# heehaw09.net
KiCad netlist of a schematic drawn in EAGLE
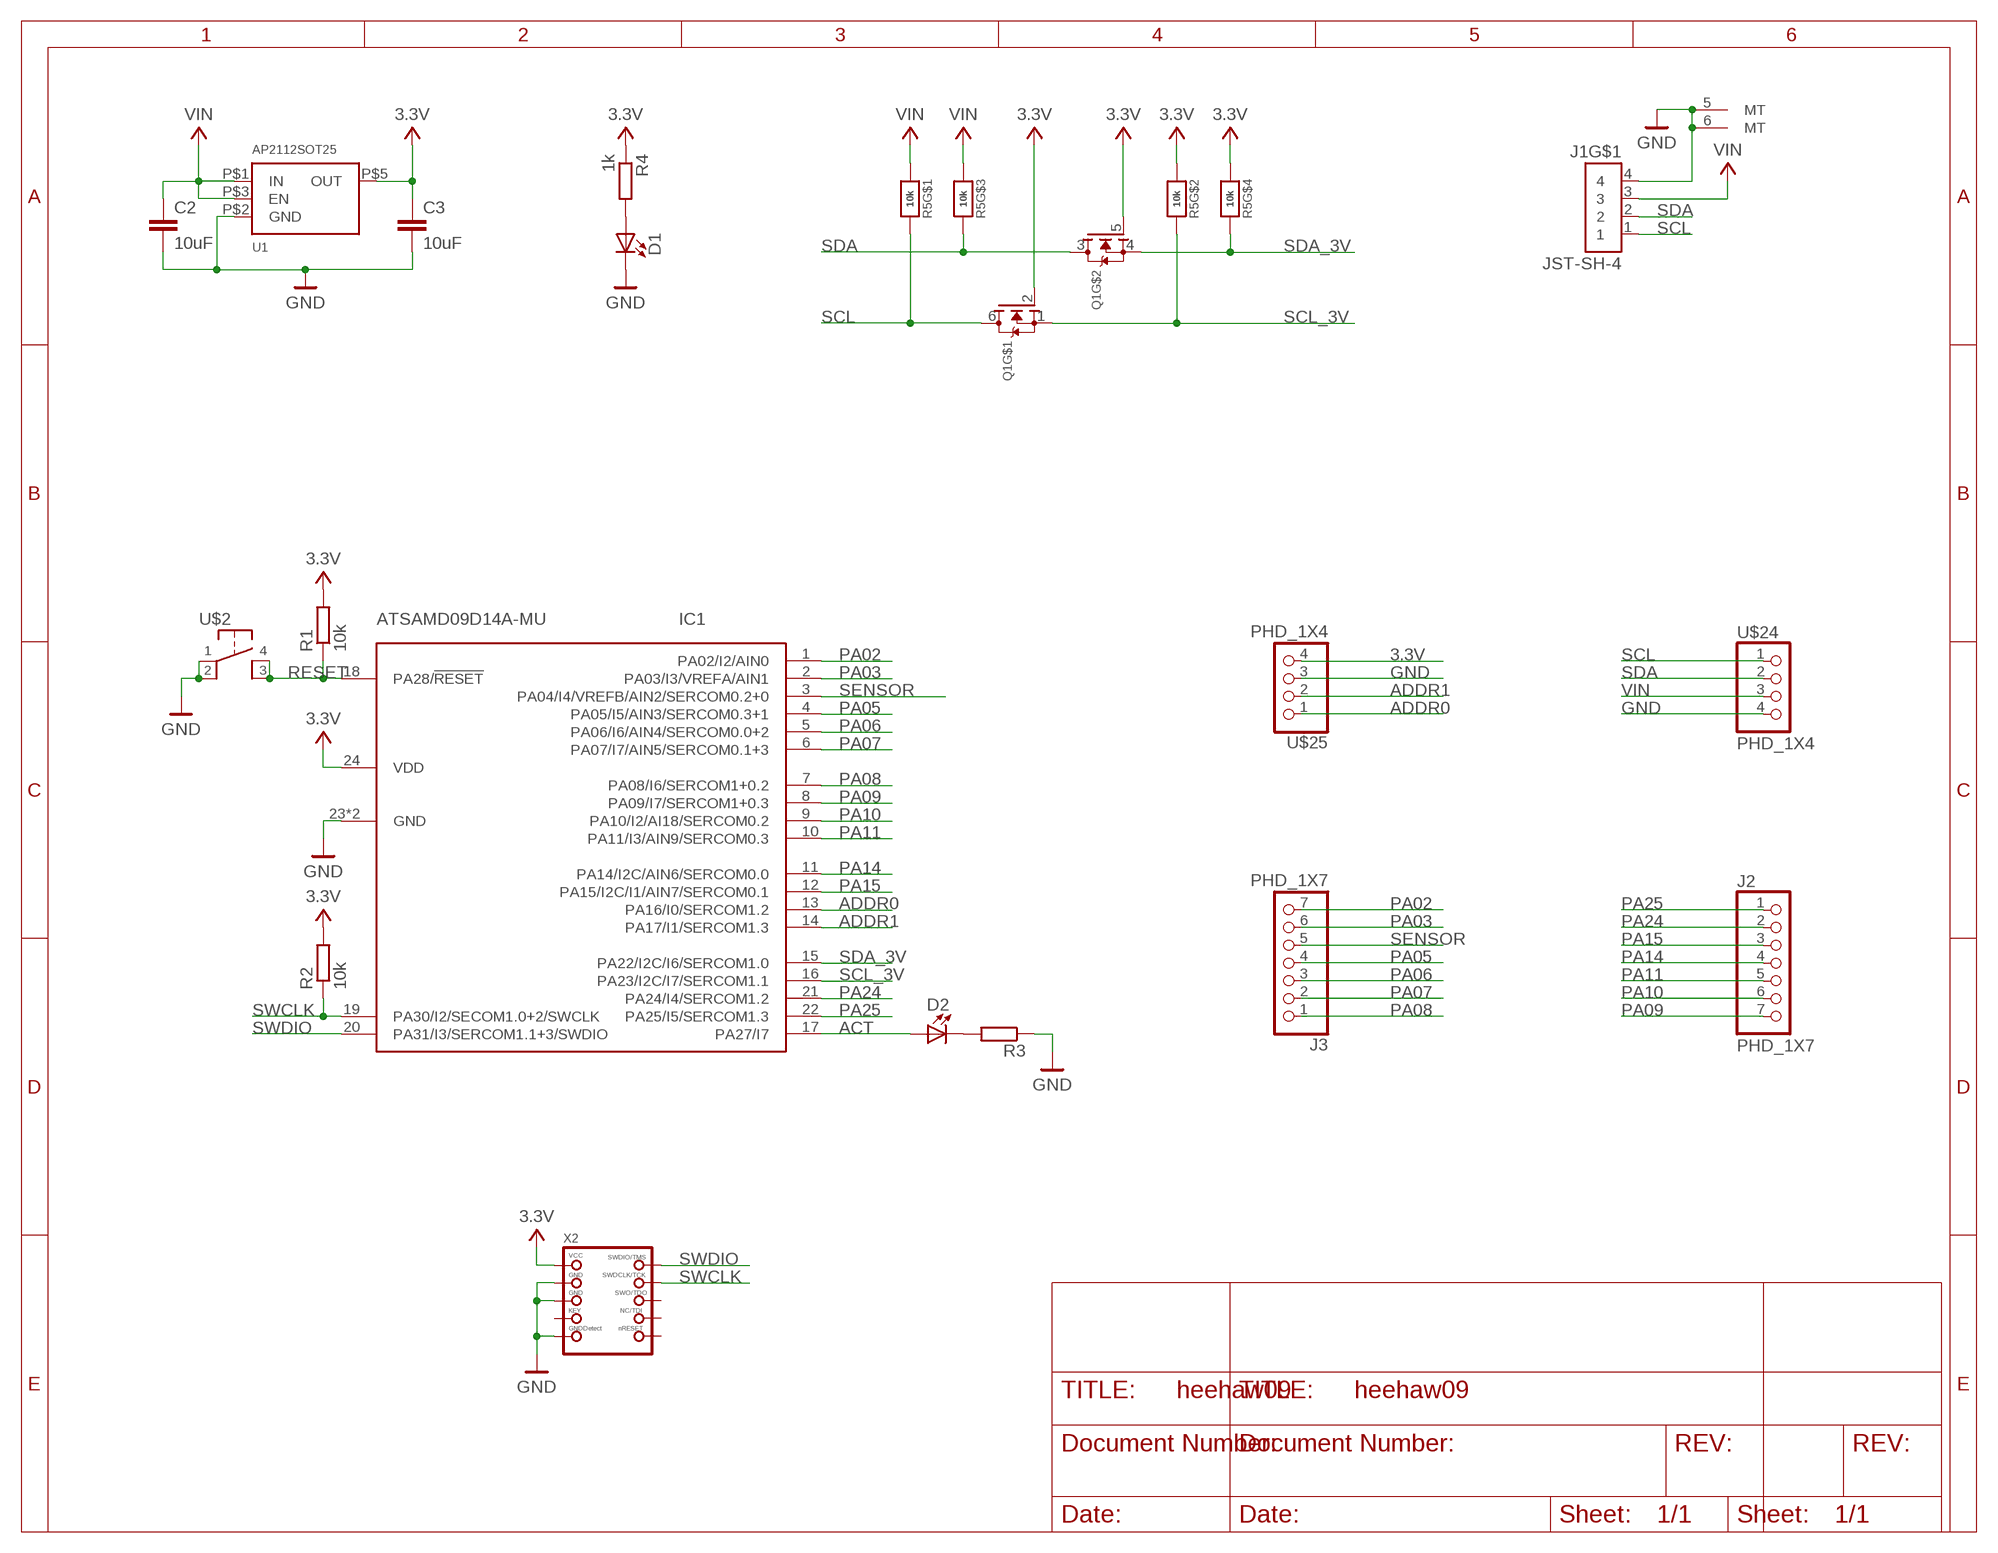
[diagram p0: schematic, sheet 1]

(export (version "E")
  (design (tool "Eeschema 10.0.6"))
  (components
    (comp (ref "C2")
      (value "10uF")
      (footprint "eagle-import:C0603")
      (libsource (lib "eagle-import") (part "C-EUC0603"))
    )
    (comp (ref "C3")
      (value "10uF")
      (footprint "eagle-import:C0603")
      (libsource (lib "eagle-import") (part "C-EUC0603"))
    )
    (comp (ref "D1")
      (value "SMD_LED0603")
      (footprint "eagle-import:LED0603")
      (libsource (lib "eagle-import") (part "SMD_LED0603"))
    )
    (comp (ref "D2")
      (value "SMD_LED0603")
      (footprint "eagle-import:LED0603")
      (libsource (lib "eagle-import") (part "SMD_LED0603"))
    )
    (comp (ref "IC1")
      (value "ATSAMD09D14A-MU")
      (footprint "eagle-import:QFN24_4MM")
      (libsource (lib "eagle-import") (part "ATSAMD09D14A-MU"))
    )
    (comp (ref "J1")
      (value "JST-SH-4")
      (footprint "eagle-import:JST-S4B-SH-SM4-TB")
      (libsource (lib "eagle-import") (part "JST-SH-4"))
    )
    (comp (ref "J2")
      (value "PHD_1X7")
      (footprint "eagle-import:PHD_1X7")
      (libsource (lib "eagle-import") (part "PHD_1X7"))
    )
    (comp (ref "J3")
      (value "PHD_1X7")
      (footprint "eagle-import:PHD_1X7")
      (libsource (lib "eagle-import") (part "PHD_1X7"))
    )
    (comp (ref "Q1")
      (value "MOSFET-N_DUAL")
      (footprint "eagle-import:SOT363")
      (libsource (lib "eagle-import") (part "MOSFET-N_DUAL"))
    )
    (comp (ref "R1")
      (value "10k")
      (footprint "eagle-import:R0603")
      (libsource (lib "eagle-import") (part "R-EU_R0603"))
    )
    (comp (ref "R2")
      (value "10k")
      (footprint "eagle-import:R0603")
      (libsource (lib "eagle-import") (part "R-EU_R0603"))
    )
    (comp (ref "R3")
      (value "R-EU_R0603")
      (footprint "eagle-import:R0603")
      (libsource (lib "eagle-import") (part "R-EU_R0603"))
    )
    (comp (ref "R4")
      (value "1k")
      (footprint "eagle-import:R0603")
      (libsource (lib "eagle-import") (part "R-EU_R0603"))
    )
    (comp (ref "R5")
      (value "10k")
      (footprint "eagle-import:RESPACK_4X0603")
      (libsource (lib "eagle-import") (part "RESISTOR_4PACK"))
    )
    (comp (ref "U$2")
      (value "PTS647")
      (footprint "eagle-import:PTS647")
      (libsource (lib "eagle-import") (part "PTS647"))
    )
    (comp (ref "U$24")
      (value "PHD_1X4")
      (footprint "eagle-import:PHD_1X4")
      (libsource (lib "eagle-import") (part "PHD_1X4"))
    )
    (comp (ref "U$25")
      (value "PHD_1X4")
      (footprint "eagle-import:PHD_1X4")
      (libsource (lib "eagle-import") (part "PHD_1X4"))
    )
    (comp (ref "U1")
      (value "AP2112SOT25")
      (footprint "eagle-import:SOT25")
      (libsource (lib "eagle-import") (part "AP2112SOT25"))
    )
    (comp (ref "X2")
      (value "SWD_2X5")
      (footprint "eagle-import:SWD_MINI")
      (libsource (lib "eagle-import") (part "SWD_2X5"))
    )
  )
  (nets
    (net (code "1") (name "/ACT") (class "Default")
      (node (ref "D2") (pin "2") (pinfunction "A_2") (pintype "passive"))
      (node (ref "IC1") (pin "17") (pinfunction "PA27/I7_17") (pintype "bidirectional"))
    )
    (net (code "2") (name "/ADDR0") (class "Default")
      (node (ref "IC1") (pin "13") (pinfunction "PA16/I0/SERCOM1.2_13") (pintype "bidirectional"))
      (node (ref "U$25") (pin "1") (pinfunction "1_1") (pintype "passive"))
    )
    (net (code "3") (name "/ADDR1") (class "Default")
      (node (ref "IC1") (pin "14") (pinfunction "PA17/I1/SERCOM1.3_14") (pintype "bidirectional"))
      (node (ref "U$25") (pin "2") (pinfunction "2_2") (pintype "passive"))
    )
    (net (code "4") (name "/PA02") (class "Default")
      (node (ref "IC1") (pin "1") (pinfunction "PA02/I2/AIN0_1") (pintype "bidirectional"))
      (node (ref "J3") (pin "7") (pinfunction "7_7") (pintype "passive"))
    )
    (net (code "5") (name "/PA03") (class "Default")
      (node (ref "IC1") (pin "2") (pinfunction "PA03/I3/VREFA/AIN1_2") (pintype "bidirectional"))
      (node (ref "J3") (pin "6") (pinfunction "6_6") (pintype "passive"))
    )
    (net (code "6") (name "/PA05") (class "Default")
      (node (ref "IC1") (pin "4") (pinfunction "PA05/I5/AIN3/SERCOM0.3+1_4") (pintype "bidirectional"))
      (node (ref "J3") (pin "4") (pinfunction "4_4") (pintype "passive"))
    )
    (net (code "7") (name "/PA06") (class "Default")
      (node (ref "IC1") (pin "5") (pinfunction "PA06/I6/AIN4/SERCOM0.0+2_5") (pintype "bidirectional"))
      (node (ref "J3") (pin "3") (pinfunction "3_3") (pintype "passive"))
    )
    (net (code "8") (name "/PA07") (class "Default")
      (node (ref "IC1") (pin "6") (pinfunction "PA07/I7/AIN5/SERCOM0.1+3_6") (pintype "bidirectional"))
      (node (ref "J3") (pin "2") (pinfunction "2_2") (pintype "passive"))
    )
    (net (code "9") (name "/PA08") (class "Default")
      (node (ref "IC1") (pin "7") (pinfunction "PA08/I6/SERCOM1+0.2_7") (pintype "bidirectional"))
      (node (ref "J3") (pin "1") (pinfunction "1_1") (pintype "passive"))
    )
    (net (code "10") (name "/PA09") (class "Default")
      (node (ref "IC1") (pin "8") (pinfunction "PA09/I7/SERCOM1+0.3_8") (pintype "bidirectional"))
      (node (ref "J2") (pin "7") (pinfunction "7_7") (pintype "passive"))
    )
    (net (code "11") (name "/PA10") (class "Default")
      (node (ref "IC1") (pin "9") (pinfunction "PA10/I2/AI18/SERCOM0.2_9") (pintype "bidirectional"))
      (node (ref "J2") (pin "6") (pinfunction "6_6") (pintype "passive"))
    )
    (net (code "12") (name "/PA11") (class "Default")
      (node (ref "IC1") (pin "10") (pinfunction "PA11/I3/AIN9/SERCOM0.3_10") (pintype "bidirectional"))
      (node (ref "J2") (pin "5") (pinfunction "5_5") (pintype "passive"))
    )
    (net (code "13") (name "/PA14") (class "Default")
      (node (ref "IC1") (pin "11") (pinfunction "PA14/I2C/AIN6/SERCOM0.0_11") (pintype "bidirectional"))
      (node (ref "J2") (pin "4") (pinfunction "4_4") (pintype "passive"))
    )
    (net (code "14") (name "/PA15") (class "Default")
      (node (ref "IC1") (pin "12") (pinfunction "PA15/I2C/I1/AIN7/SERCOM0.1_12") (pintype "bidirectional"))
      (node (ref "J2") (pin "3") (pinfunction "3_3") (pintype "passive"))
    )
    (net (code "15") (name "/PA24") (class "Default")
      (node (ref "IC1") (pin "21") (pinfunction "PA24/I4/SERCOM1.2_21") (pintype "bidirectional"))
      (node (ref "J2") (pin "2") (pinfunction "2_2") (pintype "passive"))
    )
    (net (code "16") (name "/PA25") (class "Default")
      (node (ref "IC1") (pin "22") (pinfunction "PA25/I5/SERCOM1.3_22") (pintype "bidirectional"))
      (node (ref "J2") (pin "1") (pinfunction "1_1") (pintype "passive"))
    )
    (net (code "17") (name "/RESET") (class "Default")
      (node (ref "IC1") (pin "18") (pinfunction "PA28/~{RESET}_18") (pintype "bidirectional"))
      (node (ref "R1") (pin "1") (pinfunction "1_1") (pintype "passive"))
      (node (ref "U$2") (pin "3") (pinfunction "3_3") (pintype "bidirectional"))
      (node (ref "U$2") (pin "4") (pinfunction "4_4") (pintype "bidirectional"))
    )
    (net (code "18") (name "/SCL") (class "Default")
      (node (ref "J1") (pin "1") (pinfunction "1_1") (pintype "bidirectional"))
      (node (ref "Q1") (pin "6") (pinfunction "D_6") (pintype "bidirectional"))
      (node (ref "R5") (pin "8") (pinfunction "2_8") (pintype "passive"))
      (node (ref "U$24") (pin "1") (pinfunction "1_1") (pintype "passive"))
    )
    (net (code "19") (name "/SCL_3V") (class "Default")
      (node (ref "IC1") (pin "16") (pinfunction "PA23/I2C/I7/SERCOM1.1_16") (pintype "bidirectional"))
      (node (ref "Q1") (pin "1") (pinfunction "S_1") (pintype "bidirectional"))
      (node (ref "R5") (pin "7") (pinfunction "2_7") (pintype "passive"))
    )
    (net (code "20") (name "/SDA") (class "Default")
      (node (ref "J1") (pin "2") (pinfunction "2_2") (pintype "bidirectional"))
      (node (ref "Q1") (pin "3") (pinfunction "D_3") (pintype "bidirectional"))
      (node (ref "R5") (pin "6") (pinfunction "2_6") (pintype "passive"))
      (node (ref "U$24") (pin "2") (pinfunction "2_2") (pintype "passive"))
    )
    (net (code "21") (name "/SDA_3V") (class "Default")
      (node (ref "IC1") (pin "15") (pinfunction "PA22/I2C/I6/SERCOM1.0_15") (pintype "bidirectional"))
      (node (ref "Q1") (pin "4") (pinfunction "S_4") (pintype "bidirectional"))
      (node (ref "R5") (pin "5") (pinfunction "2_5") (pintype "passive"))
    )
    (net (code "22") (name "/SENSOR") (class "Default")
      (node (ref "IC1") (pin "3") (pinfunction "PA04/I4/VREFB/AIN2/SERCOM0.2+0_3") (pintype "bidirectional"))
      (node (ref "J3") (pin "5") (pinfunction "5_5") (pintype "passive"))
    )
    (net (code "23") (name "/SWCLK") (class "Default")
      (node (ref "IC1") (pin "19") (pinfunction "PA30/I2/SECOM1.0+2/SWCLK_19") (pintype "bidirectional"))
      (node (ref "R2") (pin "1") (pinfunction "1_1") (pintype "passive"))
      (node (ref "X2") (pin "4") (pinfunction "SWDCLK_4") (pintype "bidirectional"))
    )
    (net (code "24") (name "/SWDIO") (class "Default")
      (node (ref "IC1") (pin "20") (pinfunction "PA31/I3/SERCOM1.1+3/SWDIO_20") (pintype "bidirectional"))
      (node (ref "X2") (pin "2") (pinfunction "SWDIO_2") (pintype "bidirectional"))
    )
    (net (code "25") (name "3.3V") (class "Default")
      (node (ref "C3") (pin "1") (pinfunction "1_1") (pintype "passive"))
      (node (ref "IC1") (pin "24") (pinfunction "VDD_24") (pintype "power_in"))
      (node (ref "Q1") (pin "2") (pinfunction "G_2") (pintype "bidirectional"))
      (node (ref "Q1") (pin "5") (pinfunction "G_5") (pintype "bidirectional"))
      (node (ref "R1") (pin "2") (pinfunction "2_2") (pintype "passive"))
      (node (ref "R2") (pin "2") (pinfunction "2_2") (pintype "passive"))
      (node (ref "R4") (pin "1") (pinfunction "1_1") (pintype "passive"))
      (node (ref "R5") (pin "2") (pinfunction "1_2") (pintype "passive"))
      (node (ref "R5") (pin "4") (pinfunction "1_4") (pintype "passive"))
      (node (ref "U$25") (pin "4") (pinfunction "4_4") (pintype "passive"))
      (node (ref "U1") (pin "P$5") (pinfunction "OUT_P$5") (pintype "power_in"))
      (node (ref "X2") (pin "1") (pinfunction "VCC_1") (pintype "power_in"))
    )
    (net (code "26") (name "GND") (class "Default")
      (node (ref "C2") (pin "2") (pinfunction "2_2") (pintype "passive"))
      (node (ref "C3") (pin "2") (pinfunction "2_2") (pintype "passive"))
      (node (ref "D1") (pin "1") (pinfunction "C_1") (pintype "passive"))
      (node (ref "IC1") (pin "23") (pinfunction "GND_23") (pintype "power_in"))
      (node (ref "IC1") (pin "THERM") (pinfunction "GND_THERM") (pintype "power_in"))
      (node (ref "J1") (pin "4") (pinfunction "4_4") (pintype "bidirectional"))
      (node (ref "J1") (pin "5") (pinfunction "MT_5") (pintype "bidirectional"))
      (node (ref "J1") (pin "6") (pinfunction "MT_6") (pintype "bidirectional"))
      (node (ref "R3") (pin "1") (pinfunction "1_1") (pintype "passive"))
      (node (ref "U$2") (pin "1") (pinfunction "1_1") (pintype "bidirectional"))
      (node (ref "U$2") (pin "2") (pinfunction "2_2") (pintype "bidirectional"))
      (node (ref "U$24") (pin "4") (pinfunction "4_4") (pintype "passive"))
      (node (ref "U$25") (pin "3") (pinfunction "3_3") (pintype "passive"))
      (node (ref "U1") (pin "P$2") (pinfunction "GND_P$2") (pintype "power_in"))
      (node (ref "X2") (pin "3") (pinfunction "GND_3") (pintype "power_in"))
      (node (ref "X2") (pin "5") (pinfunction "GND_5") (pintype "power_in"))
      (node (ref "X2") (pin "9") (pinfunction "GNDDETECT_9") (pintype "bidirectional"))
    )
    (net (code "27") (name "Net-(D1-A)") (class "Default")
      (node (ref "D1") (pin "2") (pinfunction "A_2") (pintype "passive"))
      (node (ref "R4") (pin "2") (pinfunction "2_2") (pintype "passive"))
    )
    (net (code "28") (name "Net-(D2-C)") (class "Default")
      (node (ref "D2") (pin "1") (pinfunction "C_1") (pintype "passive"))
      (node (ref "R3") (pin "2") (pinfunction "2_2") (pintype "passive"))
    )
    (net (code "29") (name "VIN") (class "Default")
      (node (ref "C2") (pin "1") (pinfunction "1_1") (pintype "passive"))
      (node (ref "J1") (pin "3") (pinfunction "3_3") (pintype "bidirectional"))
      (node (ref "R5") (pin "1") (pinfunction "1_1") (pintype "passive"))
      (node (ref "R5") (pin "3") (pinfunction "1_3") (pintype "passive"))
      (node (ref "U$24") (pin "3") (pinfunction "3_3") (pintype "passive"))
      (node (ref "U1") (pin "P$1") (pinfunction "IN_P$1") (pintype "power_in"))
      (node (ref "U1") (pin "P$3") (pinfunction "EN_P$3") (pintype "input"))
    )
    (net (code "30") (name "unconnected-(X2-KEY-Pad7)") (class "Default")
      (node (ref "X2") (pin "7") (pinfunction "KEY_7") (pintype "bidirectional"))
    )
    (net (code "31") (name "unconnected-(X2-NRESET-Pad10)") (class "Default")
      (node (ref "X2") (pin "10") (pinfunction "NRESET_10") (pintype "bidirectional"))
    )
    (net (code "32") (name "unconnected-(X2-SWO-Pad6)") (class "Default")
      (node (ref "X2") (pin "6") (pinfunction "SWO_6") (pintype "bidirectional"))
    )
    (net (code "33") (name "unconnected-(X2-TDI-Pad8)") (class "Default")
      (node (ref "X2") (pin "8") (pinfunction "TDI_8") (pintype "bidirectional"))
    )
  )
)
